# Voltage_Amp.net
KiCad netlist of a schematic drawn in EAGLE
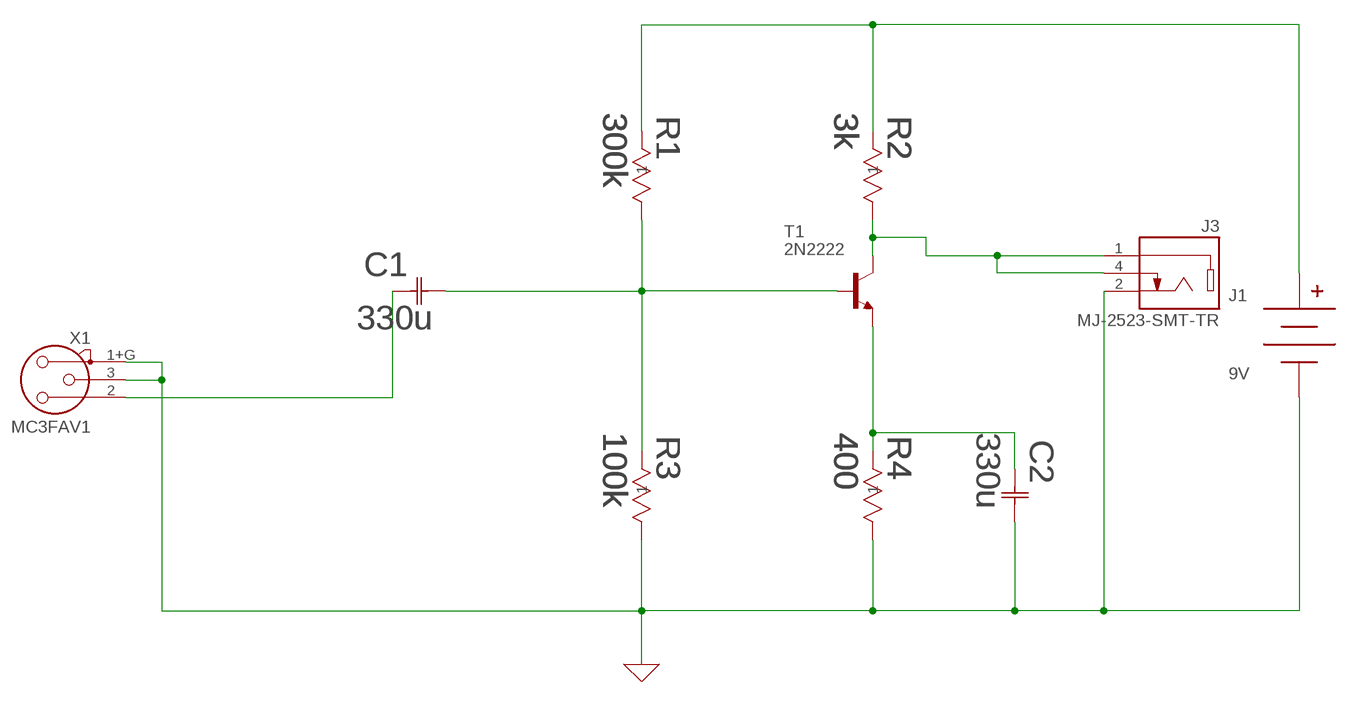
[diagram p0: schematic, sheet 1]

(export (version "E")
  (design (tool "Eeschema 10.0.6"))
  (components
    (comp (ref "C1")
      (value "330u")
      (footprint "eagle-import:U1-Z_NCH")
      (fields (field (name "MANUFACTURER_PART_NUMBER") "UKZ1E331MHM"))
      (libsource (lib "eagle-import") (part "UKZ1E331MHM"))
    )
    (comp (ref "C2")
      (value "330u")
      (footprint "eagle-import:U1-Z_NCH")
      (fields (field (name "MANUFACTURER_PART_NUMBER") "UKZ1E331MHM"))
      (libsource (lib "eagle-import") (part "UKZ1E331MHM"))
    )
    (comp (ref "J1")
      (value "9V")
      (footprint "eagle-import:BC9VPC")
      (libsource (lib "eagle-import") (part "BC9VPC"))
    )
    (comp (ref "J3")
      (value "MJ-2523-SMT-TR")
      (footprint "eagle-import:MJ-2523-SMT-TR")
      (fields (field (name "MANUFACTURER") "CUI Devices") (field (name "CREATED_BY") "PCBLayout.com"))
      (libsource (lib "eagle-import") (part "MJ-2523-SMT-TR"))
    )
    (comp (ref "R1")
      (value "300k")
      (footprint "eagle-import:CMF55")
      (fields (field (name "MANUFACTURER_PART_NUMBER") "RN55E3003BB14"))
      (libsource (lib "eagle-import") (part "RN55E3003BB14"))
    )
    (comp (ref "R2")
      (value "3k")
      (footprint "eagle-import:CMF55")
      (fields (field (name "MANUFACTURER_PART_NUMBER") "RN55C3001BB14"))
      (libsource (lib "eagle-import") (part "RN55C3001BB14"))
    )
    (comp (ref "R3")
      (value "100k")
      (footprint "eagle-import:CMF55")
      (fields (field (name "MANUFACTURER_PART_NUMBER") "RN55E1003BB14"))
      (libsource (lib "eagle-import") (part "RN55E1003BB14"))
    )
    (comp (ref "R4")
      (value "400")
      (footprint "eagle-import:CMF55")
      (fields (field (name "MANUFACTURER_PART_NUMBER") "RN55E4000BRE6"))
      (libsource (lib "eagle-import") (part "RN55E4000BRE6"))
    )
    (comp (ref "T1")
      (value "2N2222")
      (footprint "eagle-import:TO18")
      (libsource (lib "eagle-import") (part "2N2222"))
    )
    (comp (ref "X1")
      (value "MC3FAV1")
      (footprint "eagle-import:NC3FAV1")
      (libsource (lib "eagle-import") (part "MC3?FAV1"))
    )
  )
  (nets
    (net (code "1") (name "GND") (class "Default")
      (node (ref "C2") (pin "2") (pinfunction "2_2") (pintype "passive"))
      (node (ref "J1") (pin "V-") (pinfunction "V-_V-") (pintype "bidirectional"))
      (node (ref "J3") (pin "2") (pinfunction "TIP_2") (pintype "passive"))
      (node (ref "R3") (pin "2") (pinfunction "2_2") (pintype "passive"))
      (node (ref "R4") (pin "2") (pinfunction "2_2") (pintype "passive"))
      (node (ref "X1") (pin "1+G") (pinfunction "1_1+G") (pintype "passive"))
      (node (ref "X1") (pin "3") (pinfunction "3_3") (pintype "passive"))
    )
    (net (code "2") (name "Net-(C1-Pad1)") (class "Default")
      (node (ref "C1") (pin "1") (pinfunction "1_1") (pintype "passive"))
      (node (ref "X1") (pin "2") (pinfunction "2_2") (pintype "passive"))
    )
    (net (code "3") (name "Net-(J1-PadV+)") (class "Default")
      (node (ref "J1") (pin "V+") (pinfunction "V+_V+") (pintype "bidirectional"))
      (node (ref "R1") (pin "1") (pinfunction "1_1") (pintype "passive"))
      (node (ref "R2") (pin "1") (pinfunction "1_1") (pintype "passive"))
    )
    (net (code "4") (name "Net-(J3-SLEEVE)") (class "Default")
      (node (ref "J3") (pin "1") (pinfunction "SLEEVE_1") (pintype "passive"))
      (node (ref "J3") (pin "4") (pinfunction "TIP_SWITCH_4") (pintype "passive"))
      (node (ref "R2") (pin "2") (pinfunction "2_2") (pintype "passive"))
      (node (ref "T1") (pin "3") (pinfunction "C_3") (pintype "passive"))
    )
    (net (code "5") (name "Net-(T1-B)") (class "Default")
      (node (ref "C1") (pin "2") (pinfunction "2_2") (pintype "passive"))
      (node (ref "R1") (pin "2") (pinfunction "2_2") (pintype "passive"))
      (node (ref "R3") (pin "1") (pinfunction "1_1") (pintype "passive"))
      (node (ref "T1") (pin "2") (pinfunction "B_2") (pintype "passive"))
    )
    (net (code "6") (name "Net-(T1-E)") (class "Default")
      (node (ref "C2") (pin "1") (pinfunction "1_1") (pintype "passive"))
      (node (ref "R4") (pin "1") (pinfunction "1_1") (pintype "passive"))
      (node (ref "T1") (pin "1") (pinfunction "E_1") (pintype "passive"))
    )
  )
)
